# LED.net
KiCad netlist of a schematic drawn in Altium Designer
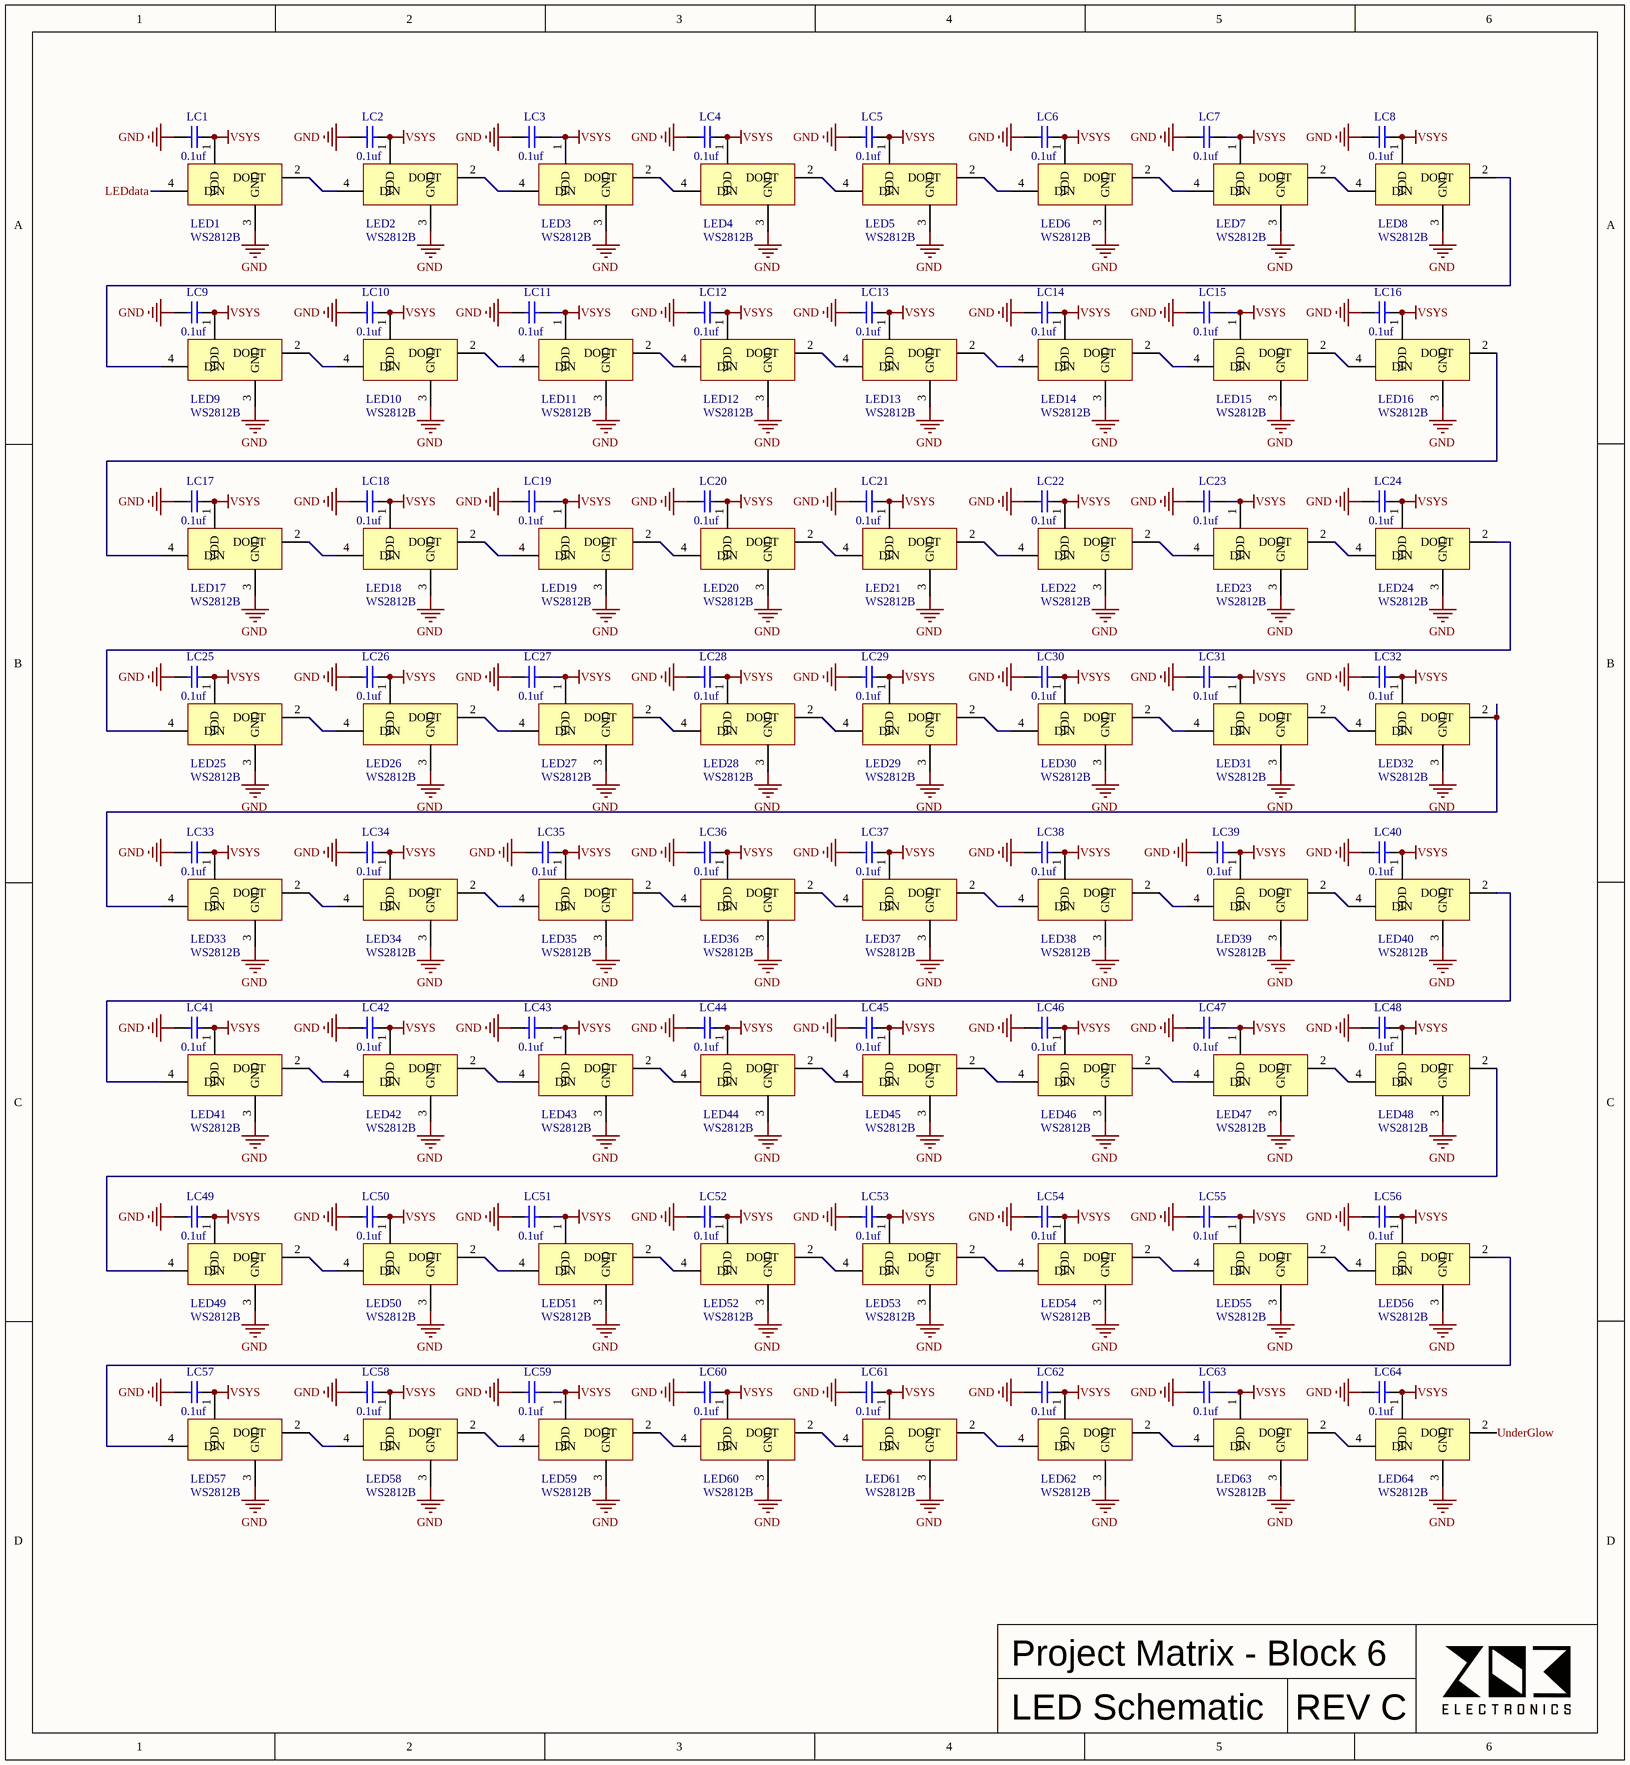
[diagram p0: LED.SchDoc]

(export (version "E")
  (design (tool "Eeschema 10.0.6"))
  (components
    (comp (ref "LC1")
      (value "0.1uf")
      (footprint "0603 CAP")
      (description "Capacitor (Semiconductor SIM Model)")
      (fields (field (name "Comment") "Cap Semi") (field (name "PUBLISHER") "Altium Limited"))
      (libsource (lib "Miscellaneous Devices") (part "Cap Semi"))
    )
    (comp (ref "LC2")
      (value "0.1uf")
      (footprint "0603 CAP")
      (description "Capacitor (Semiconductor SIM Model)")
      (fields (field (name "Comment") "Cap Semi") (field (name "PUBLISHER") "Altium Limited"))
      (libsource (lib "Miscellaneous Devices") (part "Cap Semi"))
    )
    (comp (ref "LC3")
      (value "0.1uf")
      (footprint "0603 CAP")
      (description "Capacitor (Semiconductor SIM Model)")
      (fields (field (name "Comment") "Cap Semi") (field (name "PUBLISHER") "Altium Limited"))
      (libsource (lib "Miscellaneous Devices") (part "Cap Semi"))
    )
    (comp (ref "LC4")
      (value "0.1uf")
      (footprint "0603 CAP")
      (description "Capacitor (Semiconductor SIM Model)")
      (fields (field (name "Comment") "Cap Semi") (field (name "PUBLISHER") "Altium Limited"))
      (libsource (lib "Miscellaneous Devices") (part "Cap Semi"))
    )
    (comp (ref "LC5")
      (value "0.1uf")
      (footprint "0603 CAP")
      (description "Capacitor (Semiconductor SIM Model)")
      (fields (field (name "Comment") "Cap Semi") (field (name "PUBLISHER") "Altium Limited"))
      (libsource (lib "Miscellaneous Devices") (part "Cap Semi"))
    )
    (comp (ref "LC6")
      (value "0.1uf")
      (footprint "0603 CAP")
      (description "Capacitor (Semiconductor SIM Model)")
      (fields (field (name "Comment") "Cap Semi") (field (name "PUBLISHER") "Altium Limited"))
      (libsource (lib "Miscellaneous Devices") (part "Cap Semi"))
    )
    (comp (ref "LC7")
      (value "0.1uf")
      (footprint "0603 CAP")
      (description "Capacitor (Semiconductor SIM Model)")
      (fields (field (name "Comment") "Cap Semi") (field (name "PUBLISHER") "Altium Limited"))
      (libsource (lib "Miscellaneous Devices") (part "Cap Semi"))
    )
    (comp (ref "LC8")
      (value "0.1uf")
      (footprint "0603 CAP")
      (description "Capacitor (Semiconductor SIM Model)")
      (fields (field (name "Comment") "Cap Semi") (field (name "PUBLISHER") "Altium Limited"))
      (libsource (lib "Miscellaneous Devices") (part "Cap Semi"))
    )
    (comp (ref "LC9")
      (value "0.1uf")
      (footprint "0603 CAP")
      (description "Capacitor (Semiconductor SIM Model)")
      (fields (field (name "Comment") "Cap Semi") (field (name "PUBLISHER") "Altium Limited"))
      (libsource (lib "Miscellaneous Devices") (part "Cap Semi"))
    )
    (comp (ref "LC10")
      (value "0.1uf")
      (footprint "0603 CAP")
      (description "Capacitor (Semiconductor SIM Model)")
      (fields (field (name "Comment") "Cap Semi") (field (name "PUBLISHER") "Altium Limited"))
      (libsource (lib "Miscellaneous Devices") (part "Cap Semi"))
    )
    (comp (ref "LC11")
      (value "0.1uf")
      (footprint "0603 CAP")
      (description "Capacitor (Semiconductor SIM Model)")
      (fields (field (name "Comment") "Cap Semi") (field (name "PUBLISHER") "Altium Limited"))
      (libsource (lib "Miscellaneous Devices") (part "Cap Semi"))
    )
    (comp (ref "LC12")
      (value "0.1uf")
      (footprint "0603 CAP")
      (description "Capacitor (Semiconductor SIM Model)")
      (fields (field (name "Comment") "Cap Semi") (field (name "PUBLISHER") "Altium Limited"))
      (libsource (lib "Miscellaneous Devices") (part "Cap Semi"))
    )
    (comp (ref "LC13")
      (value "0.1uf")
      (footprint "0603 CAP")
      (description "Capacitor (Semiconductor SIM Model)")
      (fields (field (name "Comment") "Cap Semi") (field (name "PUBLISHER") "Altium Limited"))
      (libsource (lib "Miscellaneous Devices") (part "Cap Semi"))
    )
    (comp (ref "LC14")
      (value "0.1uf")
      (footprint "0603 CAP")
      (description "Capacitor (Semiconductor SIM Model)")
      (fields (field (name "Comment") "Cap Semi") (field (name "PUBLISHER") "Altium Limited"))
      (libsource (lib "Miscellaneous Devices") (part "Cap Semi"))
    )
    (comp (ref "LC15")
      (value "0.1uf")
      (footprint "0603 CAP")
      (description "Capacitor (Semiconductor SIM Model)")
      (fields (field (name "Comment") "Cap Semi") (field (name "PUBLISHER") "Altium Limited"))
      (libsource (lib "Miscellaneous Devices") (part "Cap Semi"))
    )
    (comp (ref "LC16")
      (value "0.1uf")
      (footprint "0603 CAP")
      (description "Capacitor (Semiconductor SIM Model)")
      (fields (field (name "Comment") "Cap Semi") (field (name "PUBLISHER") "Altium Limited"))
      (libsource (lib "Miscellaneous Devices") (part "Cap Semi"))
    )
    (comp (ref "LC17")
      (value "0.1uf")
      (footprint "0603 CAP")
      (description "Capacitor (Semiconductor SIM Model)")
      (fields (field (name "Comment") "Cap Semi") (field (name "PUBLISHER") "Altium Limited"))
      (libsource (lib "Miscellaneous Devices") (part "Cap Semi"))
    )
    (comp (ref "LC18")
      (value "0.1uf")
      (footprint "0603 CAP")
      (description "Capacitor (Semiconductor SIM Model)")
      (fields (field (name "Comment") "Cap Semi") (field (name "PUBLISHER") "Altium Limited"))
      (libsource (lib "Miscellaneous Devices") (part "Cap Semi"))
    )
    (comp (ref "LC19")
      (value "0.1uf")
      (footprint "0603 CAP")
      (description "Capacitor (Semiconductor SIM Model)")
      (fields (field (name "Comment") "Cap Semi") (field (name "PUBLISHER") "Altium Limited"))
      (libsource (lib "Miscellaneous Devices") (part "Cap Semi"))
    )
    (comp (ref "LC20")
      (value "0.1uf")
      (footprint "0603 CAP")
      (description "Capacitor (Semiconductor SIM Model)")
      (fields (field (name "Comment") "Cap Semi") (field (name "PUBLISHER") "Altium Limited"))
      (libsource (lib "Miscellaneous Devices") (part "Cap Semi"))
    )
    (comp (ref "LC21")
      (value "0.1uf")
      (footprint "0603 CAP")
      (description "Capacitor (Semiconductor SIM Model)")
      (fields (field (name "Comment") "Cap Semi") (field (name "PUBLISHER") "Altium Limited"))
      (libsource (lib "Miscellaneous Devices") (part "Cap Semi"))
    )
    (comp (ref "LC22")
      (value "0.1uf")
      (footprint "0603 CAP")
      (description "Capacitor (Semiconductor SIM Model)")
      (fields (field (name "Comment") "Cap Semi") (field (name "PUBLISHER") "Altium Limited"))
      (libsource (lib "Miscellaneous Devices") (part "Cap Semi"))
    )
    (comp (ref "LC23")
      (value "0.1uf")
      (footprint "0603 CAP")
      (description "Capacitor (Semiconductor SIM Model)")
      (fields (field (name "Comment") "Cap Semi") (field (name "PUBLISHER") "Altium Limited"))
      (libsource (lib "Miscellaneous Devices") (part "Cap Semi"))
    )
    (comp (ref "LC24")
      (value "0.1uf")
      (footprint "0603 CAP")
      (description "Capacitor (Semiconductor SIM Model)")
      (fields (field (name "Comment") "Cap Semi") (field (name "PUBLISHER") "Altium Limited"))
      (libsource (lib "Miscellaneous Devices") (part "Cap Semi"))
    )
    (comp (ref "LC25")
      (value "0.1uf")
      (footprint "0603 CAP")
      (description "Capacitor (Semiconductor SIM Model)")
      (fields (field (name "Comment") "Cap Semi") (field (name "PUBLISHER") "Altium Limited"))
      (libsource (lib "Miscellaneous Devices") (part "Cap Semi"))
    )
    (comp (ref "LC26")
      (value "0.1uf")
      (footprint "0603 CAP")
      (description "Capacitor (Semiconductor SIM Model)")
      (fields (field (name "Comment") "Cap Semi") (field (name "PUBLISHER") "Altium Limited"))
      (libsource (lib "Miscellaneous Devices") (part "Cap Semi"))
    )
    (comp (ref "LC27")
      (value "0.1uf")
      (footprint "0603 CAP")
      (description "Capacitor (Semiconductor SIM Model)")
      (fields (field (name "Comment") "Cap Semi") (field (name "PUBLISHER") "Altium Limited"))
      (libsource (lib "Miscellaneous Devices") (part "Cap Semi"))
    )
    (comp (ref "LC28")
      (value "0.1uf")
      (footprint "0603 CAP")
      (description "Capacitor (Semiconductor SIM Model)")
      (fields (field (name "Comment") "Cap Semi") (field (name "PUBLISHER") "Altium Limited"))
      (libsource (lib "Miscellaneous Devices") (part "Cap Semi"))
    )
    (comp (ref "LC29")
      (value "0.1uf")
      (footprint "0603 CAP")
      (description "Capacitor (Semiconductor SIM Model)")
      (fields (field (name "Comment") "Cap Semi") (field (name "PUBLISHER") "Altium Limited"))
      (libsource (lib "Miscellaneous Devices") (part "Cap Semi"))
    )
    (comp (ref "LC30")
      (value "0.1uf")
      (footprint "0603 CAP")
      (description "Capacitor (Semiconductor SIM Model)")
      (fields (field (name "Comment") "Cap Semi") (field (name "PUBLISHER") "Altium Limited"))
      (libsource (lib "Miscellaneous Devices") (part "Cap Semi"))
    )
    (comp (ref "LC31")
      (value "0.1uf")
      (footprint "0603 CAP")
      (description "Capacitor (Semiconductor SIM Model)")
      (fields (field (name "Comment") "Cap Semi") (field (name "PUBLISHER") "Altium Limited"))
      (libsource (lib "Miscellaneous Devices") (part "Cap Semi"))
    )
    (comp (ref "LC32")
      (value "0.1uf")
      (footprint "0603 CAP")
      (description "Capacitor (Semiconductor SIM Model)")
      (fields (field (name "Comment") "Cap Semi") (field (name "PUBLISHER") "Altium Limited"))
      (libsource (lib "Miscellaneous Devices") (part "Cap Semi"))
    )
    (comp (ref "LC33")
      (value "0.1uf")
      (footprint "0603 CAP")
      (description "Capacitor (Semiconductor SIM Model)")
      (fields (field (name "Comment") "Cap Semi") (field (name "PUBLISHER") "Altium Limited"))
      (libsource (lib "Miscellaneous Devices") (part "Cap Semi"))
    )
    (comp (ref "LC34")
      (value "0.1uf")
      (footprint "0603 CAP")
      (description "Capacitor (Semiconductor SIM Model)")
      (fields (field (name "Comment") "Cap Semi") (field (name "PUBLISHER") "Altium Limited"))
      (libsource (lib "Miscellaneous Devices") (part "Cap Semi"))
    )
    (comp (ref "LC35")
      (value "0.1uf")
      (footprint "0603 CAP")
      (description "Capacitor (Semiconductor SIM Model)")
      (fields (field (name "Comment") "Cap Semi") (field (name "PUBLISHER") "Altium Limited"))
      (libsource (lib "Miscellaneous Devices") (part "Cap Semi"))
    )
    (comp (ref "LC36")
      (value "0.1uf")
      (footprint "0603 CAP")
      (description "Capacitor (Semiconductor SIM Model)")
      (fields (field (name "Comment") "Cap Semi") (field (name "PUBLISHER") "Altium Limited"))
      (libsource (lib "Miscellaneous Devices") (part "Cap Semi"))
    )
    (comp (ref "LC37")
      (value "0.1uf")
      (footprint "0603 CAP")
      (description "Capacitor (Semiconductor SIM Model)")
      (fields (field (name "Comment") "Cap Semi") (field (name "PUBLISHER") "Altium Limited"))
      (libsource (lib "Miscellaneous Devices") (part "Cap Semi"))
    )
    (comp (ref "LC38")
      (value "0.1uf")
      (footprint "0603 CAP")
      (description "Capacitor (Semiconductor SIM Model)")
      (fields (field (name "Comment") "Cap Semi") (field (name "PUBLISHER") "Altium Limited"))
      (libsource (lib "Miscellaneous Devices") (part "Cap Semi"))
    )
    (comp (ref "LC39")
      (value "0.1uf")
      (footprint "0603 CAP")
      (description "Capacitor (Semiconductor SIM Model)")
      (fields (field (name "Comment") "Cap Semi") (field (name "PUBLISHER") "Altium Limited"))
      (libsource (lib "Miscellaneous Devices") (part "Cap Semi"))
    )
    (comp (ref "LC40")
      (value "0.1uf")
      (footprint "0603 CAP")
      (description "Capacitor (Semiconductor SIM Model)")
      (fields (field (name "Comment") "Cap Semi") (field (name "PUBLISHER") "Altium Limited"))
      (libsource (lib "Miscellaneous Devices") (part "Cap Semi"))
    )
    (comp (ref "LC41")
      (value "0.1uf")
      (footprint "0603 CAP")
      (description "Capacitor (Semiconductor SIM Model)")
      (fields (field (name "Comment") "Cap Semi") (field (name "PUBLISHER") "Altium Limited"))
      (libsource (lib "Miscellaneous Devices") (part "Cap Semi"))
    )
    (comp (ref "LC42")
      (value "0.1uf")
      (footprint "0603 CAP")
      (description "Capacitor (Semiconductor SIM Model)")
      (fields (field (name "Comment") "Cap Semi") (field (name "PUBLISHER") "Altium Limited"))
      (libsource (lib "Miscellaneous Devices") (part "Cap Semi"))
    )
    (comp (ref "LC43")
      (value "0.1uf")
      (footprint "0603 CAP")
      (description "Capacitor (Semiconductor SIM Model)")
      (fields (field (name "Comment") "Cap Semi") (field (name "PUBLISHER") "Altium Limited"))
      (libsource (lib "Miscellaneous Devices") (part "Cap Semi"))
    )
    (comp (ref "LC44")
      (value "0.1uf")
      (footprint "0603 CAP")
      (description "Capacitor (Semiconductor SIM Model)")
      (fields (field (name "Comment") "Cap Semi") (field (name "PUBLISHER") "Altium Limited"))
      (libsource (lib "Miscellaneous Devices") (part "Cap Semi"))
    )
    (comp (ref "LC45")
      (value "0.1uf")
      (footprint "0603 CAP")
      (description "Capacitor (Semiconductor SIM Model)")
      (fields (field (name "Comment") "Cap Semi") (field (name "PUBLISHER") "Altium Limited"))
      (libsource (lib "Miscellaneous Devices") (part "Cap Semi"))
    )
    (comp (ref "LC46")
      (value "0.1uf")
      (footprint "0603 CAP")
      (description "Capacitor (Semiconductor SIM Model)")
      (fields (field (name "Comment") "Cap Semi") (field (name "PUBLISHER") "Altium Limited"))
      (libsource (lib "Miscellaneous Devices") (part "Cap Semi"))
    )
    (comp (ref "LC47")
      (value "0.1uf")
      (footprint "0603 CAP")
      (description "Capacitor (Semiconductor SIM Model)")
      (fields (field (name "Comment") "Cap Semi") (field (name "PUBLISHER") "Altium Limited"))
      (libsource (lib "Miscellaneous Devices") (part "Cap Semi"))
    )
    (comp (ref "LC48")
      (value "0.1uf")
      (footprint "0603 CAP")
      (description "Capacitor (Semiconductor SIM Model)")
      (fields (field (name "Comment") "Cap Semi") (field (name "PUBLISHER") "Altium Limited"))
      (libsource (lib "Miscellaneous Devices") (part "Cap Semi"))
    )
    (comp (ref "LC49")
      (value "0.1uf")
      (footprint "0603 CAP")
      (description "Capacitor (Semiconductor SIM Model)")
      (fields (field (name "Comment") "Cap Semi") (field (name "PUBLISHER") "Altium Limited"))
      (libsource (lib "Miscellaneous Devices") (part "Cap Semi"))
    )
    (comp (ref "LC50")
      (value "0.1uf")
      (footprint "0603 CAP")
      (description "Capacitor (Semiconductor SIM Model)")
      (fields (field (name "Comment") "Cap Semi") (field (name "PUBLISHER") "Altium Limited"))
      (libsource (lib "Miscellaneous Devices") (part "Cap Semi"))
    )
    (comp (ref "LC51")
      (value "0.1uf")
      (footprint "0603 CAP")
      (description "Capacitor (Semiconductor SIM Model)")
      (fields (field (name "Comment") "Cap Semi") (field (name "PUBLISHER") "Altium Limited"))
      (libsource (lib "Miscellaneous Devices") (part "Cap Semi"))
    )
    (comp (ref "LC52")
      (value "0.1uf")
      (footprint "0603 CAP")
      (description "Capacitor (Semiconductor SIM Model)")
      (fields (field (name "Comment") "Cap Semi") (field (name "PUBLISHER") "Altium Limited"))
      (libsource (lib "Miscellaneous Devices") (part "Cap Semi"))
    )
    (comp (ref "LC53")
      (value "0.1uf")
      (footprint "0603 CAP")
      (description "Capacitor (Semiconductor SIM Model)")
      (fields (field (name "Comment") "Cap Semi") (field (name "PUBLISHER") "Altium Limited"))
      (libsource (lib "Miscellaneous Devices") (part "Cap Semi"))
    )
    (comp (ref "LC54")
      (value "0.1uf")
      (footprint "0603 CAP")
      (description "Capacitor (Semiconductor SIM Model)")
      (fields (field (name "Comment") "Cap Semi") (field (name "PUBLISHER") "Altium Limited"))
      (libsource (lib "Miscellaneous Devices") (part "Cap Semi"))
    )
    (comp (ref "LC55")
      (value "0.1uf")
      (footprint "0603 CAP")
      (description "Capacitor (Semiconductor SIM Model)")
      (fields (field (name "Comment") "Cap Semi") (field (name "PUBLISHER") "Altium Limited"))
      (libsource (lib "Miscellaneous Devices") (part "Cap Semi"))
    )
    (comp (ref "LC56")
      (value "0.1uf")
      (footprint "0603 CAP")
      (description "Capacitor (Semiconductor SIM Model)")
      (fields (field (name "Comment") "Cap Semi") (field (name "PUBLISHER") "Altium Limited"))
      (libsource (lib "Miscellaneous Devices") (part "Cap Semi"))
    )
    (comp (ref "LC57")
      (value "0.1uf")
      (footprint "0603 CAP")
      (description "Capacitor (Semiconductor SIM Model)")
      (fields (field (name "Comment") "Cap Semi") (field (name "PUBLISHER") "Altium Limited"))
      (libsource (lib "Miscellaneous Devices") (part "Cap Semi"))
    )
    (comp (ref "LC58")
      (value "0.1uf")
      (footprint "0603 CAP")
      (description "Capacitor (Semiconductor SIM Model)")
      (fields (field (name "Comment") "Cap Semi") (field (name "PUBLISHER") "Altium Limited"))
      (libsource (lib "Miscellaneous Devices") (part "Cap Semi"))
    )
    (comp (ref "LC59")
      (value "0.1uf")
      (footprint "0603 CAP")
      (description "Capacitor (Semiconductor SIM Model)")
      (fields (field (name "Comment") "Cap Semi") (field (name "PUBLISHER") "Altium Limited"))
      (libsource (lib "Miscellaneous Devices") (part "Cap Semi"))
    )
    (comp (ref "LC60")
      (value "0.1uf")
      (footprint "0603 CAP")
      (description "Capacitor (Semiconductor SIM Model)")
      (fields (field (name "Comment") "Cap Semi") (field (name "PUBLISHER") "Altium Limited"))
      (libsource (lib "Miscellaneous Devices") (part "Cap Semi"))
    )
    (comp (ref "LC61")
      (value "0.1uf")
      (footprint "0603 CAP")
      (description "Capacitor (Semiconductor SIM Model)")
      (fields (field (name "Comment") "Cap Semi") (field (name "PUBLISHER") "Altium Limited"))
      (libsource (lib "Miscellaneous Devices") (part "Cap Semi"))
    )
    (comp (ref "LC62")
      (value "0.1uf")
      (footprint "0603 CAP")
      (description "Capacitor (Semiconductor SIM Model)")
      (fields (field (name "Comment") "Cap Semi") (field (name "PUBLISHER") "Altium Limited"))
      (libsource (lib "Miscellaneous Devices") (part "Cap Semi"))
    )
    (comp (ref "LC63")
      (value "0.1uf")
      (footprint "0603 CAP")
      (description "Capacitor (Semiconductor SIM Model)")
      (fields (field (name "Comment") "Cap Semi") (field (name "PUBLISHER") "Altium Limited"))
      (libsource (lib "Miscellaneous Devices") (part "Cap Semi"))
    )
    (comp (ref "LC64")
      (value "0.1uf")
      (footprint "0603 CAP")
      (description "Capacitor (Semiconductor SIM Model)")
      (fields (field (name "Comment") "Cap Semi") (field (name "PUBLISHER") "Altium Limited"))
      (libsource (lib "Miscellaneous Devices") (part "Cap Semi"))
    )
    (comp (ref "LED1")
      (value "WS2812B")
      (footprint "WS2812B")
      (description "3535")
      (libsource (lib "203") (part "WS2812B"))
    )
    (comp (ref "LED2")
      (value "WS2812B")
      (footprint "WS2812B")
      (description "3535")
      (libsource (lib "203") (part "WS2812B"))
    )
    (comp (ref "LED3")
      (value "WS2812B")
      (footprint "WS2812B")
      (description "3535")
      (libsource (lib "203") (part "WS2812B"))
    )
    (comp (ref "LED4")
      (value "WS2812B")
      (footprint "WS2812B")
      (description "3535")
      (libsource (lib "203") (part "WS2812B"))
    )
    (comp (ref "LED5")
      (value "WS2812B")
      (footprint "WS2812B")
      (description "3535")
      (libsource (lib "203") (part "WS2812B"))
    )
    (comp (ref "LED6")
      (value "WS2812B")
      (footprint "WS2812B")
      (description "3535")
      (libsource (lib "203") (part "WS2812B"))
    )
    (comp (ref "LED7")
      (value "WS2812B")
      (footprint "WS2812B")
      (description "3535")
      (libsource (lib "203") (part "WS2812B"))
    )
    (comp (ref "LED8")
      (value "WS2812B")
      (footprint "WS2812B")
      (description "3535")
      (libsource (lib "203") (part "WS2812B"))
    )
    (comp (ref "LED9")
      (value "WS2812B")
      (footprint "WS2812B")
      (description "3535")
      (libsource (lib "203") (part "WS2812B"))
    )
    (comp (ref "LED10")
      (value "WS2812B")
      (footprint "WS2812B")
      (description "3535")
      (libsource (lib "203") (part "WS2812B"))
    )
    (comp (ref "LED11")
      (value "WS2812B")
      (footprint "WS2812B")
      (description "3535")
      (libsource (lib "203") (part "WS2812B"))
    )
    (comp (ref "LED12")
      (value "WS2812B")
      (footprint "WS2812B")
      (description "3535")
      (libsource (lib "203") (part "WS2812B"))
    )
    (comp (ref "LED13")
      (value "WS2812B")
      (footprint "WS2812B")
      (description "3535")
      (libsource (lib "203") (part "WS2812B"))
    )
    (comp (ref "LED14")
      (value "WS2812B")
      (footprint "WS2812B")
      (description "3535")
      (libsource (lib "203") (part "WS2812B"))
    )
    (comp (ref "LED15")
      (value "WS2812B")
      (footprint "WS2812B")
      (description "3535")
      (libsource (lib "203") (part "WS2812B"))
    )
    (comp (ref "LED16")
      (value "WS2812B")
      (footprint "WS2812B")
      (description "3535")
      (libsource (lib "203") (part "WS2812B"))
    )
    (comp (ref "LED17")
      (value "WS2812B")
      (footprint "WS2812B")
      (description "3535")
      (libsource (lib "203") (part "WS2812B"))
    )
    (comp (ref "LED18")
      (value "WS2812B")
      (footprint "WS2812B")
      (description "3535")
      (libsource (lib "203") (part "WS2812B"))
    )
    (comp (ref "LED19")
      (value "WS2812B")
      (footprint "WS2812B")
      (description "3535")
      (libsource (lib "203") (part "WS2812B"))
    )
    (comp (ref "LED20")
      (value "WS2812B")
      (footprint "WS2812B")
      (description "3535")
      (libsource (lib "203") (part "WS2812B"))
    )
    (comp (ref "LED21")
      (value "WS2812B")
      (footprint "WS2812B")
      (description "3535")
      (libsource (lib "203") (part "WS2812B"))
    )
    (comp (ref "LED22")
      (value "WS2812B")
      (footprint "WS2812B")
      (description "3535")
      (libsource (lib "203") (part "WS2812B"))
    )
    (comp (ref "LED23")
      (value "WS2812B")
      (footprint "WS2812B")
      (description "3535")
      (libsource (lib "203") (part "WS2812B"))
    )
    (comp (ref "LED24")
      (value "WS2812B")
      (footprint "WS2812B")
      (description "3535")
      (libsource (lib "203") (part "WS2812B"))
    )
    (comp (ref "LED25")
      (value "WS2812B")
      (footprint "WS2812B")
      (description "3535")
      (libsource (lib "203") (part "WS2812B"))
    )
    (comp (ref "LED26")
      (value "WS2812B")
      (footprint "WS2812B")
      (description "3535")
      (libsource (lib "203") (part "WS2812B"))
    )
    (comp (ref "LED27")
      (value "WS2812B")
      (footprint "WS2812B")
      (description "3535")
      (libsource (lib "203") (part "WS2812B"))
    )
    (comp (ref "LED28")
      (value "WS2812B")
      (footprint "WS2812B")
      (description "3535")
      (libsource (lib "203") (part "WS2812B"))
    )
    (comp (ref "LED29")
      (value "WS2812B")
      (footprint "WS2812B")
      (description "3535")
      (libsource (lib "203") (part "WS2812B"))
    )
    (comp (ref "LED30")
      (value "WS2812B")
      (footprint "WS2812B")
      (description "3535")
      (libsource (lib "203") (part "WS2812B"))
    )
    (comp (ref "LED31")
      (value "WS2812B")
      (footprint "WS2812B")
      (description "3535")
      (libsource (lib "203") (part "WS2812B"))
    )
    (comp (ref "LED32")
      (value "WS2812B")
      (footprint "WS2812B")
      (description "3535")
      (libsource (lib "203") (part "WS2812B"))
    )
    (comp (ref "LED33")
      (value "WS2812B")
      (footprint "WS2812B")
      (description "3535")
      (libsource (lib "203") (part "WS2812B"))
    )
    (comp (ref "LED34")
      (value "WS2812B")
      (footprint "WS2812B")
      (description "3535")
      (libsource (lib "203") (part "WS2812B"))
    )
    (comp (ref "LED35")
      (value "WS2812B")
      (footprint "WS2812B")
      (description "3535")
      (libsource (lib "203") (part "WS2812B"))
    )
    (comp (ref "LED36")
      (value "WS2812B")
      (footprint "WS2812B")
      (description "3535")
      (libsource (lib "203") (part "WS2812B"))
    )
    (comp (ref "LED37")
      (value "WS2812B")
      (footprint "WS2812B")
      (description "3535")
      (libsource (lib "203") (part "WS2812B"))
    )
    (comp (ref "LED38")
      (value "WS2812B")
      (footprint "WS2812B")
      (description "3535")
      (libsource (lib "203") (part "WS2812B"))
    )
    (comp (ref "LED39")
      (value "WS2812B")
      (footprint "WS2812B")
      (description "3535")
      (libsource (lib "203") (part "WS2812B"))
    )
    (comp (ref "LED40")
      (value "WS2812B")
      (footprint "WS2812B")
      (description "3535")
      (libsource (lib "203") (part "WS2812B"))
    )
    (comp (ref "LED41")
      (value "WS2812B")
      (footprint "WS2812B")
      (description "3535")
      (libsource (lib "203") (part "WS2812B"))
    )
    (comp (ref "LED42")
      (value "WS2812B")
      (footprint "WS2812B")
      (description "3535")
      (libsource (lib "203") (part "WS2812B"))
    )
    (comp (ref "LED43")
      (value "WS2812B")
      (footprint "WS2812B")
      (description "3535")
      (libsource (lib "203") (part "WS2812B"))
    )
    (comp (ref "LED44")
      (value "WS2812B")
      (footprint "WS2812B")
      (description "3535")
      (libsource (lib "203") (part "WS2812B"))
    )
    (comp (ref "LED45")
      (value "WS2812B")
      (footprint "WS2812B")
      (description "3535")
      (libsource (lib "203") (part "WS2812B"))
    )
    (comp (ref "LED46")
      (value "WS2812B")
      (footprint "WS2812B")
      (description "3535")
      (libsource (lib "203") (part "WS2812B"))
    )
    (comp (ref "LED47")
      (value "WS2812B")
      (footprint "WS2812B")
      (description "3535")
      (libsource (lib "203") (part "WS2812B"))
    )
    (comp (ref "LED48")
      (value "WS2812B")
      (footprint "WS2812B")
      (description "3535")
      (libsource (lib "203") (part "WS2812B"))
    )
    (comp (ref "LED49")
      (value "WS2812B")
      (footprint "WS2812B")
      (description "3535")
      (libsource (lib "203") (part "WS2812B"))
    )
    (comp (ref "LED50")
      (value "WS2812B")
      (footprint "WS2812B")
      (description "3535")
      (libsource (lib "203") (part "WS2812B"))
    )
    (comp (ref "LED51")
      (value "WS2812B")
      (footprint "WS2812B")
      (description "3535")
      (libsource (lib "203") (part "WS2812B"))
    )
    (comp (ref "LED52")
      (value "WS2812B")
      (footprint "WS2812B")
      (description "3535")
      (libsource (lib "203") (part "WS2812B"))
    )
    (comp (ref "LED53")
      (value "WS2812B")
      (footprint "WS2812B")
      (description "3535")
      (libsource (lib "203") (part "WS2812B"))
    )
    (comp (ref "LED54")
      (value "WS2812B")
      (footprint "WS2812B")
      (description "3535")
      (libsource (lib "203") (part "WS2812B"))
    )
    (comp (ref "LED55")
      (value "WS2812B")
      (footprint "WS2812B")
      (description "3535")
      (libsource (lib "203") (part "WS2812B"))
    )
    (comp (ref "LED56")
      (value "WS2812B")
      (footprint "WS2812B")
      (description "3535")
      (libsource (lib "203") (part "WS2812B"))
    )
    (comp (ref "LED57")
      (value "WS2812B")
      (footprint "WS2812B")
      (description "3535")
      (libsource (lib "203") (part "WS2812B"))
    )
    (comp (ref "LED58")
      (value "WS2812B")
      (footprint "WS2812B")
      (description "3535")
      (libsource (lib "203") (part "WS2812B"))
    )
    (comp (ref "LED59")
      (value "WS2812B")
      (footprint "WS2812B")
      (description "3535")
      (libsource (lib "203") (part "WS2812B"))
    )
    (comp (ref "LED60")
      (value "WS2812B")
      (footprint "WS2812B")
      (description "3535")
      (libsource (lib "203") (part "WS2812B"))
    )
    (comp (ref "LED61")
      (value "WS2812B")
      (footprint "WS2812B")
      (description "3535")
      (libsource (lib "203") (part "WS2812B"))
    )
    (comp (ref "LED62")
      (value "WS2812B")
      (footprint "WS2812B")
      (description "3535")
      (libsource (lib "203") (part "WS2812B"))
    )
    (comp (ref "LED63")
      (value "WS2812B")
      (footprint "WS2812B")
      (description "3535")
      (libsource (lib "203") (part "WS2812B"))
    )
    (comp (ref "LED64")
      (value "WS2812B")
      (footprint "WS2812B")
      (description "3535")
      (libsource (lib "203") (part "WS2812B"))
    )
  )
  (nets
    (net (code "1") (name "/LEDdata") (class "Default")
      (node (ref "LED1") (pin "4") (pinfunction "DIN_4") (pintype "passive"))
    )
    (net (code "2") (name "/UnderGlow") (class "Default")
      (node (ref "LED64") (pin "2") (pinfunction "DOUT_2") (pintype "passive"))
    )
    (net (code "3") (name "GND") (class "Default")
      (node (ref "LC1") (pin "1") (pinfunction "1_1") (pintype "passive"))
      (node (ref "LC10") (pin "1") (pinfunction "1_1") (pintype "passive"))
      (node (ref "LC11") (pin "1") (pinfunction "1_1") (pintype "passive"))
      (node (ref "LC12") (pin "1") (pinfunction "1_1") (pintype "passive"))
      (node (ref "LC13") (pin "1") (pinfunction "1_1") (pintype "passive"))
      (node (ref "LC14") (pin "1") (pinfunction "1_1") (pintype "passive"))
      (node (ref "LC15") (pin "1") (pinfunction "1_1") (pintype "passive"))
      (node (ref "LC16") (pin "1") (pinfunction "1_1") (pintype "passive"))
      (node (ref "LC17") (pin "1") (pinfunction "1_1") (pintype "passive"))
      (node (ref "LC18") (pin "1") (pinfunction "1_1") (pintype "passive"))
      (node (ref "LC19") (pin "1") (pinfunction "1_1") (pintype "passive"))
      (node (ref "LC2") (pin "1") (pinfunction "1_1") (pintype "passive"))
      (node (ref "LC20") (pin "1") (pinfunction "1_1") (pintype "passive"))
      (node (ref "LC21") (pin "1") (pinfunction "1_1") (pintype "passive"))
      (node (ref "LC22") (pin "1") (pinfunction "1_1") (pintype "passive"))
      (node (ref "LC23") (pin "1") (pinfunction "1_1") (pintype "passive"))
      (node (ref "LC24") (pin "1") (pinfunction "1_1") (pintype "passive"))
      (node (ref "LC25") (pin "1") (pinfunction "1_1") (pintype "passive"))
      (node (ref "LC26") (pin "1") (pinfunction "1_1") (pintype "passive"))
      (node (ref "LC27") (pin "1") (pinfunction "1_1") (pintype "passive"))
      (node (ref "LC28") (pin "1") (pinfunction "1_1") (pintype "passive"))
      (node (ref "LC29") (pin "1") (pinfunction "1_1") (pintype "passive"))
      (node (ref "LC3") (pin "1") (pinfunction "1_1") (pintype "passive"))
      (node (ref "LC30") (pin "1") (pinfunction "1_1") (pintype "passive"))
      (node (ref "LC31") (pin "1") (pinfunction "1_1") (pintype "passive"))
      (node (ref "LC32") (pin "1") (pinfunction "1_1") (pintype "passive"))
      (node (ref "LC33") (pin "1") (pinfunction "1_1") (pintype "passive"))
      (node (ref "LC34") (pin "1") (pinfunction "1_1") (pintype "passive"))
      (node (ref "LC35") (pin "1") (pinfunction "1_1") (pintype "passive"))
      (node (ref "LC36") (pin "1") (pinfunction "1_1") (pintype "passive"))
      (node (ref "LC37") (pin "1") (pinfunction "1_1") (pintype "passive"))
      (node (ref "LC38") (pin "1") (pinfunction "1_1") (pintype "passive"))
      (node (ref "LC39") (pin "1") (pinfunction "1_1") (pintype "passive"))
      (node (ref "LC4") (pin "1") (pinfunction "1_1") (pintype "passive"))
      (node (ref "LC40") (pin "1") (pinfunction "1_1") (pintype "passive"))
      (node (ref "LC41") (pin "1") (pinfunction "1_1") (pintype "passive"))
      (node (ref "LC42") (pin "1") (pinfunction "1_1") (pintype "passive"))
      (node (ref "LC43") (pin "1") (pinfunction "1_1") (pintype "passive"))
      (node (ref "LC44") (pin "1") (pinfunction "1_1") (pintype "passive"))
      (node (ref "LC45") (pin "1") (pinfunction "1_1") (pintype "passive"))
      (node (ref "LC46") (pin "1") (pinfunction "1_1") (pintype "passive"))
      (node (ref "LC47") (pin "1") (pinfunction "1_1") (pintype "passive"))
      (node (ref "LC48") (pin "1") (pinfunction "1_1") (pintype "passive"))
      (node (ref "LC49") (pin "1") (pinfunction "1_1") (pintype "passive"))
      (node (ref "LC5") (pin "1") (pinfunction "1_1") (pintype "passive"))
      (node (ref "LC50") (pin "1") (pinfunction "1_1") (pintype "passive"))
      (node (ref "LC51") (pin "1") (pinfunction "1_1") (pintype "passive"))
      (node (ref "LC52") (pin "1") (pinfunction "1_1") (pintype "passive"))
      (node (ref "LC53") (pin "1") (pinfunction "1_1") (pintype "passive"))
      (node (ref "LC54") (pin "1") (pinfunction "1_1") (pintype "passive"))
      (node (ref "LC55") (pin "1") (pinfunction "1_1") (pintype "passive"))
      (node (ref "LC56") (pin "1") (pinfunction "1_1") (pintype "passive"))
      (node (ref "LC57") (pin "1") (pinfunction "1_1") (pintype "passive"))
      (node (ref "LC58") (pin "1") (pinfunction "1_1") (pintype "passive"))
      (node (ref "LC59") (pin "1") (pinfunction "1_1") (pintype "passive"))
      (node (ref "LC6") (pin "1") (pinfunction "1_1") (pintype "passive"))
      (node (ref "LC60") (pin "1") (pinfunction "1_1") (pintype "passive"))
      (node (ref "LC61") (pin "1") (pinfunction "1_1") (pintype "passive"))
      (node (ref "LC62") (pin "1") (pinfunction "1_1") (pintype "passive"))
      (node (ref "LC63") (pin "1") (pinfunction "1_1") (pintype "passive"))
      (node (ref "LC64") (pin "1") (pinfunction "1_1") (pintype "passive"))
      (node (ref "LC7") (pin "1") (pinfunction "1_1") (pintype "passive"))
      (node (ref "LC8") (pin "1") (pinfunction "1_1") (pintype "passive"))
      (node (ref "LC9") (pin "1") (pinfunction "1_1") (pintype "passive"))
      (node (ref "LED1") (pin "3") (pinfunction "GND_3") (pintype "passive"))
      (node (ref "LED10") (pin "3") (pinfunction "GND_3") (pintype "passive"))
      (node (ref "LED11") (pin "3") (pinfunction "GND_3") (pintype "passive"))
      (node (ref "LED12") (pin "3") (pinfunction "GND_3") (pintype "passive"))
      (node (ref "LED13") (pin "3") (pinfunction "GND_3") (pintype "passive"))
      (node (ref "LED14") (pin "3") (pinfunction "GND_3") (pintype "passive"))
      (node (ref "LED15") (pin "3") (pinfunction "GND_3") (pintype "passive"))
      (node (ref "LED16") (pin "3") (pinfunction "GND_3") (pintype "passive"))
      (node (ref "LED17") (pin "3") (pinfunction "GND_3") (pintype "passive"))
      (node (ref "LED18") (pin "3") (pinfunction "GND_3") (pintype "passive"))
      (node (ref "LED19") (pin "3") (pinfunction "GND_3") (pintype "passive"))
      (node (ref "LED2") (pin "3") (pinfunction "GND_3") (pintype "passive"))
      (node (ref "LED20") (pin "3") (pinfunction "GND_3") (pintype "passive"))
      (node (ref "LED21") (pin "3") (pinfunction "GND_3") (pintype "passive"))
      (node (ref "LED22") (pin "3") (pinfunction "GND_3") (pintype "passive"))
      (node (ref "LED23") (pin "3") (pinfunction "GND_3") (pintype "passive"))
      (node (ref "LED24") (pin "3") (pinfunction "GND_3") (pintype "passive"))
      (node (ref "LED25") (pin "3") (pinfunction "GND_3") (pintype "passive"))
      (node (ref "LED26") (pin "3") (pinfunction "GND_3") (pintype "passive"))
      (node (ref "LED27") (pin "3") (pinfunction "GND_3") (pintype "passive"))
      (node (ref "LED28") (pin "3") (pinfunction "GND_3") (pintype "passive"))
      (node (ref "LED29") (pin "3") (pinfunction "GND_3") (pintype "passive"))
      (node (ref "LED3") (pin "3") (pinfunction "GND_3") (pintype "passive"))
      (node (ref "LED30") (pin "3") (pinfunction "GND_3") (pintype "passive"))
      (node (ref "LED31") (pin "3") (pinfunction "GND_3") (pintype "passive"))
      (node (ref "LED32") (pin "3") (pinfunction "GND_3") (pintype "passive"))
      (node (ref "LED33") (pin "3") (pinfunction "GND_3") (pintype "passive"))
      (node (ref "LED34") (pin "3") (pinfunction "GND_3") (pintype "passive"))
      (node (ref "LED35") (pin "3") (pinfunction "GND_3") (pintype "passive"))
      (node (ref "LED36") (pin "3") (pinfunction "GND_3") (pintype "passive"))
      (node (ref "LED37") (pin "3") (pinfunction "GND_3") (pintype "passive"))
      (node (ref "LED38") (pin "3") (pinfunction "GND_3") (pintype "passive"))
      (node (ref "LED39") (pin "3") (pinfunction "GND_3") (pintype "passive"))
      (node (ref "LED4") (pin "3") (pinfunction "GND_3") (pintype "passive"))
      (node (ref "LED40") (pin "3") (pinfunction "GND_3") (pintype "passive"))
      (node (ref "LED41") (pin "3") (pinfunction "GND_3") (pintype "passive"))
      (node (ref "LED42") (pin "3") (pinfunction "GND_3") (pintype "passive"))
      (node (ref "LED43") (pin "3") (pinfunction "GND_3") (pintype "passive"))
      (node (ref "LED44") (pin "3") (pinfunction "GND_3") (pintype "passive"))
      (node (ref "LED45") (pin "3") (pinfunction "GND_3") (pintype "passive"))
      (node (ref "LED46") (pin "3") (pinfunction "GND_3") (pintype "passive"))
      (node (ref "LED47") (pin "3") (pinfunction "GND_3") (pintype "passive"))
      (node (ref "LED48") (pin "3") (pinfunction "GND_3") (pintype "passive"))
      (node (ref "LED49") (pin "3") (pinfunction "GND_3") (pintype "passive"))
      (node (ref "LED5") (pin "3") (pinfunction "GND_3") (pintype "passive"))
      (node (ref "LED50") (pin "3") (pinfunction "GND_3") (pintype "passive"))
      (node (ref "LED51") (pin "3") (pinfunction "GND_3") (pintype "passive"))
      (node (ref "LED52") (pin "3") (pinfunction "GND_3") (pintype "passive"))
      (node (ref "LED53") (pin "3") (pinfunction "GND_3") (pintype "passive"))
      (node (ref "LED54") (pin "3") (pinfunction "GND_3") (pintype "passive"))
      (node (ref "LED55") (pin "3") (pinfunction "GND_3") (pintype "passive"))
      (node (ref "LED56") (pin "3") (pinfunction "GND_3") (pintype "passive"))
      (node (ref "LED57") (pin "3") (pinfunction "GND_3") (pintype "passive"))
      (node (ref "LED58") (pin "3") (pinfunction "GND_3") (pintype "passive"))
      (node (ref "LED59") (pin "3") (pinfunction "GND_3") (pintype "passive"))
      (node (ref "LED6") (pin "3") (pinfunction "GND_3") (pintype "passive"))
      (node (ref "LED60") (pin "3") (pinfunction "GND_3") (pintype "passive"))
      (node (ref "LED61") (pin "3") (pinfunction "GND_3") (pintype "passive"))
      (node (ref "LED62") (pin "3") (pinfunction "GND_3") (pintype "passive"))
      (node (ref "LED63") (pin "3") (pinfunction "GND_3") (pintype "passive"))
      (node (ref "LED64") (pin "3") (pinfunction "GND_3") (pintype "passive"))
      (node (ref "LED7") (pin "3") (pinfunction "GND_3") (pintype "passive"))
      (node (ref "LED8") (pin "3") (pinfunction "GND_3") (pintype "passive"))
      (node (ref "LED9") (pin "3") (pinfunction "GND_3") (pintype "passive"))
    )
    (net (code "4") (name "Net-(LED1-DOUT)") (class "Default")
      (node (ref "LED1") (pin "2") (pinfunction "DOUT_2") (pintype "passive"))
      (node (ref "LED2") (pin "4") (pinfunction "DIN_4") (pintype "passive"))
    )
    (net (code "5") (name "Net-(LED2-DOUT)") (class "Default")
      (node (ref "LED2") (pin "2") (pinfunction "DOUT_2") (pintype "passive"))
      (node (ref "LED3") (pin "4") (pinfunction "DIN_4") (pintype "passive"))
    )
    (net (code "6") (name "Net-(LED3-DOUT)") (class "Default")
      (node (ref "LED3") (pin "2") (pinfunction "DOUT_2") (pintype "passive"))
      (node (ref "LED4") (pin "4") (pinfunction "DIN_4") (pintype "passive"))
    )
    (net (code "7") (name "Net-(LED4-DOUT)") (class "Default")
      (node (ref "LED4") (pin "2") (pinfunction "DOUT_2") (pintype "passive"))
      (node (ref "LED5") (pin "4") (pinfunction "DIN_4") (pintype "passive"))
    )
    (net (code "8") (name "Net-(LED5-DOUT)") (class "Default")
      (node (ref "LED5") (pin "2") (pinfunction "DOUT_2") (pintype "passive"))
      (node (ref "LED6") (pin "4") (pinfunction "DIN_4") (pintype "passive"))
    )
    (net (code "9") (name "Net-(LED6-DOUT)") (class "Default")
      (node (ref "LED6") (pin "2") (pinfunction "DOUT_2") (pintype "passive"))
      (node (ref "LED7") (pin "4") (pinfunction "DIN_4") (pintype "passive"))
    )
    (net (code "10") (name "Net-(LED7-DOUT)") (class "Default")
      (node (ref "LED7") (pin "2") (pinfunction "DOUT_2") (pintype "passive"))
      (node (ref "LED8") (pin "4") (pinfunction "DIN_4") (pintype "passive"))
    )
    (net (code "11") (name "Net-(LED8-DOUT)") (class "Default")
      (node (ref "LED8") (pin "2") (pinfunction "DOUT_2") (pintype "passive"))
      (node (ref "LED9") (pin "4") (pinfunction "DIN_4") (pintype "passive"))
    )
    (net (code "12") (name "Net-(LED10-DIN)") (class "Default")
      (node (ref "LED10") (pin "4") (pinfunction "DIN_4") (pintype "passive"))
      (node (ref "LED9") (pin "2") (pinfunction "DOUT_2") (pintype "passive"))
    )
    (net (code "13") (name "Net-(LED10-DOUT)") (class "Default")
      (node (ref "LED10") (pin "2") (pinfunction "DOUT_2") (pintype "passive"))
      (node (ref "LED11") (pin "4") (pinfunction "DIN_4") (pintype "passive"))
    )
    (net (code "14") (name "Net-(LED11-DOUT)") (class "Default")
      (node (ref "LED11") (pin "2") (pinfunction "DOUT_2") (pintype "passive"))
      (node (ref "LED12") (pin "4") (pinfunction "DIN_4") (pintype "passive"))
    )
    (net (code "15") (name "Net-(LED12-DOUT)") (class "Default")
      (node (ref "LED12") (pin "2") (pinfunction "DOUT_2") (pintype "passive"))
      (node (ref "LED13") (pin "4") (pinfunction "DIN_4") (pintype "passive"))
    )
    (net (code "16") (name "Net-(LED13-DOUT)") (class "Default")
      (node (ref "LED13") (pin "2") (pinfunction "DOUT_2") (pintype "passive"))
      (node (ref "LED14") (pin "4") (pinfunction "DIN_4") (pintype "passive"))
    )
    (net (code "17") (name "Net-(LED14-DOUT)") (class "Default")
      (node (ref "LED14") (pin "2") (pinfunction "DOUT_2") (pintype "passive"))
      (node (ref "LED15") (pin "4") (pinfunction "DIN_4") (pintype "passive"))
    )
    (net (code "18") (name "Net-(LED15-DOUT)") (class "Default")
      (node (ref "LED15") (pin "2") (pinfunction "DOUT_2") (pintype "passive"))
      (node (ref "LED16") (pin "4") (pinfunction "DIN_4") (pintype "passive"))
    )
    (net (code "19") (name "Net-(LED16-DOUT)") (class "Default")
      (node (ref "LED16") (pin "2") (pinfunction "DOUT_2") (pintype "passive"))
      (node (ref "LED17") (pin "4") (pinfunction "DIN_4") (pintype "passive"))
    )
    (net (code "20") (name "Net-(LED17-DOUT)") (class "Default")
      (node (ref "LED17") (pin "2") (pinfunction "DOUT_2") (pintype "passive"))
      (node (ref "LED18") (pin "4") (pinfunction "DIN_4") (pintype "passive"))
    )
    (net (code "21") (name "Net-(LED18-DOUT)") (class "Default")
      (node (ref "LED18") (pin "2") (pinfunction "DOUT_2") (pintype "passive"))
      (node (ref "LED19") (pin "4") (pinfunction "DIN_4") (pintype "passive"))
    )
    (net (code "22") (name "Net-(LED19-DOUT)") (class "Default")
      (node (ref "LED19") (pin "2") (pinfunction "DOUT_2") (pintype "passive"))
      (node (ref "LED20") (pin "4") (pinfunction "DIN_4") (pintype "passive"))
    )
    (net (code "23") (name "Net-(LED20-DOUT)") (class "Default")
      (node (ref "LED20") (pin "2") (pinfunction "DOUT_2") (pintype "passive"))
      (node (ref "LED21") (pin "4") (pinfunction "DIN_4") (pintype "passive"))
    )
    (net (code "24") (name "Net-(LED21-DOUT)") (class "Default")
      (node (ref "LED21") (pin "2") (pinfunction "DOUT_2") (pintype "passive"))
      (node (ref "LED22") (pin "4") (pinfunction "DIN_4") (pintype "passive"))
    )
    (net (code "25") (name "Net-(LED22-DOUT)") (class "Default")
      (node (ref "LED22") (pin "2") (pinfunction "DOUT_2") (pintype "passive"))
      (node (ref "LED23") (pin "4") (pinfunction "DIN_4") (pintype "passive"))
    )
    (net (code "26") (name "Net-(LED23-DOUT)") (class "Default")
      (node (ref "LED23") (pin "2") (pinfunction "DOUT_2") (pintype "passive"))
      (node (ref "LED24") (pin "4") (pinfunction "DIN_4") (pintype "passive"))
    )
    (net (code "27") (name "Net-(LED24-DOUT)") (class "Default")
      (node (ref "LED24") (pin "2") (pinfunction "DOUT_2") (pintype "passive"))
      (node (ref "LED25") (pin "4") (pinfunction "DIN_4") (pintype "passive"))
    )
    (net (code "28") (name "Net-(LED25-DOUT)") (class "Default")
      (node (ref "LED25") (pin "2") (pinfunction "DOUT_2") (pintype "passive"))
      (node (ref "LED26") (pin "4") (pinfunction "DIN_4") (pintype "passive"))
    )
    (net (code "29") (name "Net-(LED26-DOUT)") (class "Default")
      (node (ref "LED26") (pin "2") (pinfunction "DOUT_2") (pintype "passive"))
      (node (ref "LED27") (pin "4") (pinfunction "DIN_4") (pintype "passive"))
    )
    (net (code "30") (name "Net-(LED27-DOUT)") (class "Default")
      (node (ref "LED27") (pin "2") (pinfunction "DOUT_2") (pintype "passive"))
      (node (ref "LED28") (pin "4") (pinfunction "DIN_4") (pintype "passive"))
    )
    (net (code "31") (name "Net-(LED28-DOUT)") (class "Default")
      (node (ref "LED28") (pin "2") (pinfunction "DOUT_2") (pintype "passive"))
      (node (ref "LED29") (pin "4") (pinfunction "DIN_4") (pintype "passive"))
    )
    (net (code "32") (name "Net-(LED29-DOUT)") (class "Default")
      (node (ref "LED29") (pin "2") (pinfunction "DOUT_2") (pintype "passive"))
      (node (ref "LED30") (pin "4") (pinfunction "DIN_4") (pintype "passive"))
    )
    (net (code "33") (name "Net-(LED30-DOUT)") (class "Default")
      (node (ref "LED30") (pin "2") (pinfunction "DOUT_2") (pintype "passive"))
      (node (ref "LED31") (pin "4") (pinfunction "DIN_4") (pintype "passive"))
    )
    (net (code "34") (name "Net-(LED31-DOUT)") (class "Default")
      (node (ref "LED31") (pin "2") (pinfunction "DOUT_2") (pintype "passive"))
      (node (ref "LED32") (pin "4") (pinfunction "DIN_4") (pintype "passive"))
    )
    (net (code "35") (name "Net-(LED32-DOUT)") (class "Default")
      (node (ref "LED32") (pin "2") (pinfunction "DOUT_2") (pintype "passive"))
      (node (ref "LED33") (pin "4") (pinfunction "DIN_4") (pintype "passive"))
    )
    (net (code "36") (name "Net-(LED33-DOUT)") (class "Default")
      (node (ref "LED33") (pin "2") (pinfunction "DOUT_2") (pintype "passive"))
      (node (ref "LED34") (pin "4") (pinfunction "DIN_4") (pintype "passive"))
    )
    (net (code "37") (name "Net-(LED34-DOUT)") (class "Default")
      (node (ref "LED34") (pin "2") (pinfunction "DOUT_2") (pintype "passive"))
      (node (ref "LED35") (pin "4") (pinfunction "DIN_4") (pintype "passive"))
    )
    (net (code "38") (name "Net-(LED35-DOUT)") (class "Default")
      (node (ref "LED35") (pin "2") (pinfunction "DOUT_2") (pintype "passive"))
      (node (ref "LED36") (pin "4") (pinfunction "DIN_4") (pintype "passive"))
    )
    (net (code "39") (name "Net-(LED36-DOUT)") (class "Default")
      (node (ref "LED36") (pin "2") (pinfunction "DOUT_2") (pintype "passive"))
      (node (ref "LED37") (pin "4") (pinfunction "DIN_4") (pintype "passive"))
    )
    (net (code "40") (name "Net-(LED37-DOUT)") (class "Default")
      (node (ref "LED37") (pin "2") (pinfunction "DOUT_2") (pintype "passive"))
      (node (ref "LED38") (pin "4") (pinfunction "DIN_4") (pintype "passive"))
    )
    (net (code "41") (name "Net-(LED38-DOUT)") (class "Default")
      (node (ref "LED38") (pin "2") (pinfunction "DOUT_2") (pintype "passive"))
      (node (ref "LED39") (pin "4") (pinfunction "DIN_4") (pintype "passive"))
    )
    (net (code "42") (name "Net-(LED39-DOUT)") (class "Default")
      (node (ref "LED39") (pin "2") (pinfunction "DOUT_2") (pintype "passive"))
      (node (ref "LED40") (pin "4") (pinfunction "DIN_4") (pintype "passive"))
    )
    (net (code "43") (name "Net-(LED40-DOUT)") (class "Default")
      (node (ref "LED40") (pin "2") (pinfunction "DOUT_2") (pintype "passive"))
      (node (ref "LED41") (pin "4") (pinfunction "DIN_4") (pintype "passive"))
    )
    (net (code "44") (name "Net-(LED41-DOUT)") (class "Default")
      (node (ref "LED41") (pin "2") (pinfunction "DOUT_2") (pintype "passive"))
      (node (ref "LED42") (pin "4") (pinfunction "DIN_4") (pintype "passive"))
    )
    (net (code "45") (name "Net-(LED42-DOUT)") (class "Default")
      (node (ref "LED42") (pin "2") (pinfunction "DOUT_2") (pintype "passive"))
      (node (ref "LED43") (pin "4") (pinfunction "DIN_4") (pintype "passive"))
    )
    (net (code "46") (name "Net-(LED43-DOUT)") (class "Default")
      (node (ref "LED43") (pin "2") (pinfunction "DOUT_2") (pintype "passive"))
      (node (ref "LED44") (pin "4") (pinfunction "DIN_4") (pintype "passive"))
    )
    (net (code "47") (name "Net-(LED44-DOUT)") (class "Default")
      (node (ref "LED44") (pin "2") (pinfunction "DOUT_2") (pintype "passive"))
      (node (ref "LED45") (pin "4") (pinfunction "DIN_4") (pintype "passive"))
    )
    (net (code "48") (name "Net-(LED45-DOUT)") (class "Default")
      (node (ref "LED45") (pin "2") (pinfunction "DOUT_2") (pintype "passive"))
      (node (ref "LED46") (pin "4") (pinfunction "DIN_4") (pintype "passive"))
    )
    (net (code "49") (name "Net-(LED46-DOUT)") (class "Default")
      (node (ref "LED46") (pin "2") (pinfunction "DOUT_2") (pintype "passive"))
      (node (ref "LED47") (pin "4") (pinfunction "DIN_4") (pintype "passive"))
    )
    (net (code "50") (name "Net-(LED47-DOUT)") (class "Default")
      (node (ref "LED47") (pin "2") (pinfunction "DOUT_2") (pintype "passive"))
      (node (ref "LED48") (pin "4") (pinfunction "DIN_4") (pintype "passive"))
    )
    (net (code "51") (name "Net-(LED48-DOUT)") (class "Default")
      (node (ref "LED48") (pin "2") (pinfunction "DOUT_2") (pintype "passive"))
      (node (ref "LED49") (pin "4") (pinfunction "DIN_4") (pintype "passive"))
    )
    (net (code "52") (name "Net-(LED49-DOUT)") (class "Default")
      (node (ref "LED49") (pin "2") (pinfunction "DOUT_2") (pintype "passive"))
      (node (ref "LED50") (pin "4") (pinfunction "DIN_4") (pintype "passive"))
    )
    (net (code "53") (name "Net-(LED50-DOUT)") (class "Default")
      (node (ref "LED50") (pin "2") (pinfunction "DOUT_2") (pintype "passive"))
      (node (ref "LED51") (pin "4") (pinfunction "DIN_4") (pintype "passive"))
    )
    (net (code "54") (name "Net-(LED51-DOUT)") (class "Default")
      (node (ref "LED51") (pin "2") (pinfunction "DOUT_2") (pintype "passive"))
      (node (ref "LED52") (pin "4") (pinfunction "DIN_4") (pintype "passive"))
    )
    (net (code "55") (name "Net-(LED52-DOUT)") (class "Default")
      (node (ref "LED52") (pin "2") (pinfunction "DOUT_2") (pintype "passive"))
      (node (ref "LED53") (pin "4") (pinfunction "DIN_4") (pintype "passive"))
    )
    (net (code "56") (name "Net-(LED53-DOUT)") (class "Default")
      (node (ref "LED53") (pin "2") (pinfunction "DOUT_2") (pintype "passive"))
      (node (ref "LED54") (pin "4") (pinfunction "DIN_4") (pintype "passive"))
    )
    (net (code "57") (name "Net-(LED54-DOUT)") (class "Default")
      (node (ref "LED54") (pin "2") (pinfunction "DOUT_2") (pintype "passive"))
      (node (ref "LED55") (pin "4") (pinfunction "DIN_4") (pintype "passive"))
    )
    (net (code "58") (name "Net-(LED55-DOUT)") (class "Default")
      (node (ref "LED55") (pin "2") (pinfunction "DOUT_2") (pintype "passive"))
      (node (ref "LED56") (pin "4") (pinfunction "DIN_4") (pintype "passive"))
    )
    (net (code "59") (name "Net-(LED56-DOUT)") (class "Default")
      (node (ref "LED56") (pin "2") (pinfunction "DOUT_2") (pintype "passive"))
      (node (ref "LED57") (pin "4") (pinfunction "DIN_4") (pintype "passive"))
    )
    (net (code "60") (name "Net-(LED57-DOUT)") (class "Default")
      (node (ref "LED57") (pin "2") (pinfunction "DOUT_2") (pintype "passive"))
      (node (ref "LED58") (pin "4") (pinfunction "DIN_4") (pintype "passive"))
    )
    (net (code "61") (name "Net-(LED58-DOUT)") (class "Default")
      (node (ref "LED58") (pin "2") (pinfunction "DOUT_2") (pintype "passive"))
      (node (ref "LED59") (pin "4") (pinfunction "DIN_4") (pintype "passive"))
    )
    (net (code "62") (name "Net-(LED59-DOUT)") (class "Default")
      (node (ref "LED59") (pin "2") (pinfunction "DOUT_2") (pintype "passive"))
      (node (ref "LED60") (pin "4") (pinfunction "DIN_4") (pintype "passive"))
    )
    (net (code "63") (name "Net-(LED60-DOUT)") (class "Default")
      (node (ref "LED60") (pin "2") (pinfunction "DOUT_2") (pintype "passive"))
      (node (ref "LED61") (pin "4") (pinfunction "DIN_4") (pintype "passive"))
    )
    (net (code "64") (name "Net-(LED61-DOUT)") (class "Default")
      (node (ref "LED61") (pin "2") (pinfunction "DOUT_2") (pintype "passive"))
      (node (ref "LED62") (pin "4") (pinfunction "DIN_4") (pintype "passive"))
    )
    (net (code "65") (name "Net-(LED62-DOUT)") (class "Default")
      (node (ref "LED62") (pin "2") (pinfunction "DOUT_2") (pintype "passive"))
      (node (ref "LED63") (pin "4") (pinfunction "DIN_4") (pintype "passive"))
    )
    (net (code "66") (name "Net-(LED63-DOUT)") (class "Default")
      (node (ref "LED63") (pin "2") (pinfunction "DOUT_2") (pintype "passive"))
      (node (ref "LED64") (pin "4") (pinfunction "DIN_4") (pintype "passive"))
    )
    (net (code "67") (name "VSYS") (class "Default")
      (node (ref "LC1") (pin "2") (pinfunction "2_2") (pintype "passive"))
      (node (ref "LC10") (pin "2") (pinfunction "2_2") (pintype "passive"))
      (node (ref "LC11") (pin "2") (pinfunction "2_2") (pintype "passive"))
      (node (ref "LC12") (pin "2") (pinfunction "2_2") (pintype "passive"))
      (node (ref "LC13") (pin "2") (pinfunction "2_2") (pintype "passive"))
      (node (ref "LC14") (pin "2") (pinfunction "2_2") (pintype "passive"))
      (node (ref "LC15") (pin "2") (pinfunction "2_2") (pintype "passive"))
      (node (ref "LC16") (pin "2") (pinfunction "2_2") (pintype "passive"))
      (node (ref "LC17") (pin "2") (pinfunction "2_2") (pintype "passive"))
      (node (ref "LC18") (pin "2") (pinfunction "2_2") (pintype "passive"))
      (node (ref "LC19") (pin "2") (pinfunction "2_2") (pintype "passive"))
      (node (ref "LC2") (pin "2") (pinfunction "2_2") (pintype "passive"))
      (node (ref "LC20") (pin "2") (pinfunction "2_2") (pintype "passive"))
      (node (ref "LC21") (pin "2") (pinfunction "2_2") (pintype "passive"))
      (node (ref "LC22") (pin "2") (pinfunction "2_2") (pintype "passive"))
      (node (ref "LC23") (pin "2") (pinfunction "2_2") (pintype "passive"))
      (node (ref "LC24") (pin "2") (pinfunction "2_2") (pintype "passive"))
      (node (ref "LC25") (pin "2") (pinfunction "2_2") (pintype "passive"))
      (node (ref "LC26") (pin "2") (pinfunction "2_2") (pintype "passive"))
      (node (ref "LC27") (pin "2") (pinfunction "2_2") (pintype "passive"))
      (node (ref "LC28") (pin "2") (pinfunction "2_2") (pintype "passive"))
      (node (ref "LC29") (pin "2") (pinfunction "2_2") (pintype "passive"))
      (node (ref "LC3") (pin "2") (pinfunction "2_2") (pintype "passive"))
      (node (ref "LC30") (pin "2") (pinfunction "2_2") (pintype "passive"))
      (node (ref "LC31") (pin "2") (pinfunction "2_2") (pintype "passive"))
      (node (ref "LC32") (pin "2") (pinfunction "2_2") (pintype "passive"))
      (node (ref "LC33") (pin "2") (pinfunction "2_2") (pintype "passive"))
      (node (ref "LC34") (pin "2") (pinfunction "2_2") (pintype "passive"))
      (node (ref "LC35") (pin "2") (pinfunction "2_2") (pintype "passive"))
      (node (ref "LC36") (pin "2") (pinfunction "2_2") (pintype "passive"))
      (node (ref "LC37") (pin "2") (pinfunction "2_2") (pintype "passive"))
      (node (ref "LC38") (pin "2") (pinfunction "2_2") (pintype "passive"))
      (node (ref "LC39") (pin "2") (pinfunction "2_2") (pintype "passive"))
      (node (ref "LC4") (pin "2") (pinfunction "2_2") (pintype "passive"))
      (node (ref "LC40") (pin "2") (pinfunction "2_2") (pintype "passive"))
      (node (ref "LC41") (pin "2") (pinfunction "2_2") (pintype "passive"))
      (node (ref "LC42") (pin "2") (pinfunction "2_2") (pintype "passive"))
      (node (ref "LC43") (pin "2") (pinfunction "2_2") (pintype "passive"))
      (node (ref "LC44") (pin "2") (pinfunction "2_2") (pintype "passive"))
      (node (ref "LC45") (pin "2") (pinfunction "2_2") (pintype "passive"))
      (node (ref "LC46") (pin "2") (pinfunction "2_2") (pintype "passive"))
      (node (ref "LC47") (pin "2") (pinfunction "2_2") (pintype "passive"))
      (node (ref "LC48") (pin "2") (pinfunction "2_2") (pintype "passive"))
      (node (ref "LC49") (pin "2") (pinfunction "2_2") (pintype "passive"))
      (node (ref "LC5") (pin "2") (pinfunction "2_2") (pintype "passive"))
      (node (ref "LC50") (pin "2") (pinfunction "2_2") (pintype "passive"))
      (node (ref "LC51") (pin "2") (pinfunction "2_2") (pintype "passive"))
      (node (ref "LC52") (pin "2") (pinfunction "2_2") (pintype "passive"))
      (node (ref "LC53") (pin "2") (pinfunction "2_2") (pintype "passive"))
      (node (ref "LC54") (pin "2") (pinfunction "2_2") (pintype "passive"))
      (node (ref "LC55") (pin "2") (pinfunction "2_2") (pintype "passive"))
      (node (ref "LC56") (pin "2") (pinfunction "2_2") (pintype "passive"))
      (node (ref "LC57") (pin "2") (pinfunction "2_2") (pintype "passive"))
      (node (ref "LC58") (pin "2") (pinfunction "2_2") (pintype "passive"))
      (node (ref "LC59") (pin "2") (pinfunction "2_2") (pintype "passive"))
      (node (ref "LC6") (pin "2") (pinfunction "2_2") (pintype "passive"))
      (node (ref "LC60") (pin "2") (pinfunction "2_2") (pintype "passive"))
      (node (ref "LC61") (pin "2") (pinfunction "2_2") (pintype "passive"))
      (node (ref "LC62") (pin "2") (pinfunction "2_2") (pintype "passive"))
      (node (ref "LC63") (pin "2") (pinfunction "2_2") (pintype "passive"))
      (node (ref "LC64") (pin "2") (pinfunction "2_2") (pintype "passive"))
      (node (ref "LC7") (pin "2") (pinfunction "2_2") (pintype "passive"))
      (node (ref "LC8") (pin "2") (pinfunction "2_2") (pintype "passive"))
      (node (ref "LC9") (pin "2") (pinfunction "2_2") (pintype "passive"))
      (node (ref "LED1") (pin "1") (pinfunction "VDD_1") (pintype "passive"))
      (node (ref "LED10") (pin "1") (pinfunction "VDD_1") (pintype "passive"))
      (node (ref "LED11") (pin "1") (pinfunction "VDD_1") (pintype "passive"))
      (node (ref "LED12") (pin "1") (pinfunction "VDD_1") (pintype "passive"))
      (node (ref "LED13") (pin "1") (pinfunction "VDD_1") (pintype "passive"))
      (node (ref "LED14") (pin "1") (pinfunction "VDD_1") (pintype "passive"))
      (node (ref "LED15") (pin "1") (pinfunction "VDD_1") (pintype "passive"))
      (node (ref "LED16") (pin "1") (pinfunction "VDD_1") (pintype "passive"))
      (node (ref "LED17") (pin "1") (pinfunction "VDD_1") (pintype "passive"))
      (node (ref "LED18") (pin "1") (pinfunction "VDD_1") (pintype "passive"))
      (node (ref "LED19") (pin "1") (pinfunction "VDD_1") (pintype "passive"))
      (node (ref "LED2") (pin "1") (pinfunction "VDD_1") (pintype "passive"))
      (node (ref "LED20") (pin "1") (pinfunction "VDD_1") (pintype "passive"))
      (node (ref "LED21") (pin "1") (pinfunction "VDD_1") (pintype "passive"))
      (node (ref "LED22") (pin "1") (pinfunction "VDD_1") (pintype "passive"))
      (node (ref "LED23") (pin "1") (pinfunction "VDD_1") (pintype "passive"))
      (node (ref "LED24") (pin "1") (pinfunction "VDD_1") (pintype "passive"))
      (node (ref "LED25") (pin "1") (pinfunction "VDD_1") (pintype "passive"))
      (node (ref "LED26") (pin "1") (pinfunction "VDD_1") (pintype "passive"))
      (node (ref "LED27") (pin "1") (pinfunction "VDD_1") (pintype "passive"))
      (node (ref "LED28") (pin "1") (pinfunction "VDD_1") (pintype "passive"))
      (node (ref "LED29") (pin "1") (pinfunction "VDD_1") (pintype "passive"))
      (node (ref "LED3") (pin "1") (pinfunction "VDD_1") (pintype "passive"))
      (node (ref "LED30") (pin "1") (pinfunction "VDD_1") (pintype "passive"))
      (node (ref "LED31") (pin "1") (pinfunction "VDD_1") (pintype "passive"))
      (node (ref "LED32") (pin "1") (pinfunction "VDD_1") (pintype "passive"))
      (node (ref "LED33") (pin "1") (pinfunction "VDD_1") (pintype "passive"))
      (node (ref "LED34") (pin "1") (pinfunction "VDD_1") (pintype "passive"))
      (node (ref "LED35") (pin "1") (pinfunction "VDD_1") (pintype "passive"))
      (node (ref "LED36") (pin "1") (pinfunction "VDD_1") (pintype "passive"))
      (node (ref "LED37") (pin "1") (pinfunction "VDD_1") (pintype "passive"))
      (node (ref "LED38") (pin "1") (pinfunction "VDD_1") (pintype "passive"))
      (node (ref "LED39") (pin "1") (pinfunction "VDD_1") (pintype "passive"))
      (node (ref "LED4") (pin "1") (pinfunction "VDD_1") (pintype "passive"))
      (node (ref "LED40") (pin "1") (pinfunction "VDD_1") (pintype "passive"))
      (node (ref "LED41") (pin "1") (pinfunction "VDD_1") (pintype "passive"))
      (node (ref "LED42") (pin "1") (pinfunction "VDD_1") (pintype "passive"))
      (node (ref "LED43") (pin "1") (pinfunction "VDD_1") (pintype "passive"))
      (node (ref "LED44") (pin "1") (pinfunction "VDD_1") (pintype "passive"))
      (node (ref "LED45") (pin "1") (pinfunction "VDD_1") (pintype "passive"))
      (node (ref "LED46") (pin "1") (pinfunction "VDD_1") (pintype "passive"))
      (node (ref "LED47") (pin "1") (pinfunction "VDD_1") (pintype "passive"))
      (node (ref "LED48") (pin "1") (pinfunction "VDD_1") (pintype "passive"))
      (node (ref "LED49") (pin "1") (pinfunction "VDD_1") (pintype "passive"))
      (node (ref "LED5") (pin "1") (pinfunction "VDD_1") (pintype "passive"))
      (node (ref "LED50") (pin "1") (pinfunction "VDD_1") (pintype "passive"))
      (node (ref "LED51") (pin "1") (pinfunction "VDD_1") (pintype "passive"))
      (node (ref "LED52") (pin "1") (pinfunction "VDD_1") (pintype "passive"))
      (node (ref "LED53") (pin "1") (pinfunction "VDD_1") (pintype "passive"))
      (node (ref "LED54") (pin "1") (pinfunction "VDD_1") (pintype "passive"))
      (node (ref "LED55") (pin "1") (pinfunction "VDD_1") (pintype "passive"))
      (node (ref "LED56") (pin "1") (pinfunction "VDD_1") (pintype "passive"))
      (node (ref "LED57") (pin "1") (pinfunction "VDD_1") (pintype "passive"))
      (node (ref "LED58") (pin "1") (pinfunction "VDD_1") (pintype "passive"))
      (node (ref "LED59") (pin "1") (pinfunction "VDD_1") (pintype "passive"))
      (node (ref "LED6") (pin "1") (pinfunction "VDD_1") (pintype "passive"))
      (node (ref "LED60") (pin "1") (pinfunction "VDD_1") (pintype "passive"))
      (node (ref "LED61") (pin "1") (pinfunction "VDD_1") (pintype "passive"))
      (node (ref "LED62") (pin "1") (pinfunction "VDD_1") (pintype "passive"))
      (node (ref "LED63") (pin "1") (pinfunction "VDD_1") (pintype "passive"))
      (node (ref "LED64") (pin "1") (pinfunction "VDD_1") (pintype "passive"))
      (node (ref "LED7") (pin "1") (pinfunction "VDD_1") (pintype "passive"))
      (node (ref "LED8") (pin "1") (pinfunction "VDD_1") (pintype "passive"))
      (node (ref "LED9") (pin "1") (pinfunction "VDD_1") (pintype "passive"))
    )
  )
)
